# Sheet1.net
KiCad netlist of a schematic drawn in Altium Designer
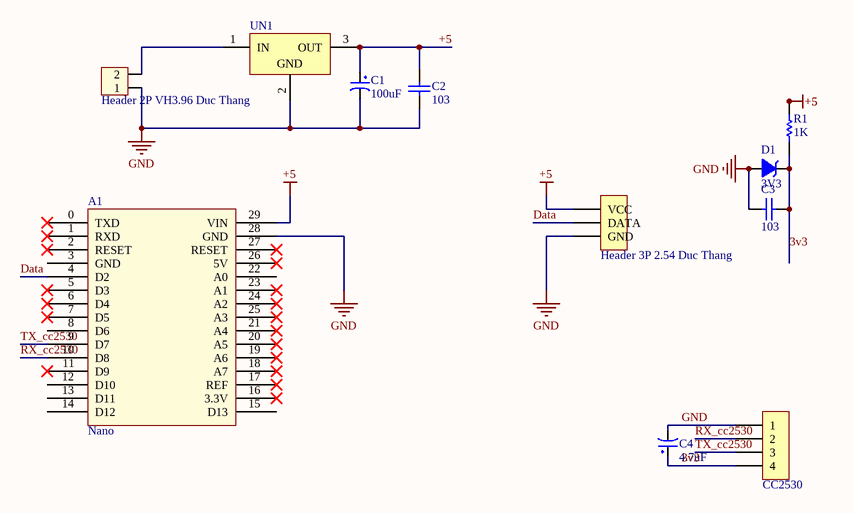
[diagram p0: Sheet1.SchDoc]

(export (version "E")
  (design (tool "Eeschema 10.0.6"))
  (components
    (comp (ref "A1")
      (value "Nano")
      (footprint "Arduino nano")
      (libsource (lib "Altium_Lib_by_KhueNguyenCreator") (part "Arduino Nano"))
    )
    (comp (ref "C1")
      (value "100uF")
      (footprint "tu hoa 5mm")
      (description "Cắm")
      (libsource (lib "Altium_Lib_by_KhueNguyenCreator") (part "Tu Hoa 100uF 16V 5x7"))
    )
    (comp (ref "C2")
      (value "103")
      (footprint "tu gom")
      (description "Cắm")
      (libsource (lib "Altium_Lib_by_KhueNguyenCreator") (part "Tu gom 103 50V"))
    )
    (comp (ref "C3")
      (value "103")
      (footprint "tu gom")
      (description "Cắm")
      (libsource (lib "Altium_Lib_by_KhueNguyenCreator") (part "Tu gom 103 50V"))
    )
    (comp (ref "C4")
      (value "4.7uF")
      (footprint "tu hoa 8mm")
      (description "Cắm")
      (libsource (lib "Altium_Lib_by_KhueNguyenCreator") (part "Tu Hoa 4.7uF 400V 8x12"))
    )
    (comp (ref "D1")
      (value "3V3")
      (footprint "DZ2A")
      (description "Diode Zenner")
      (libsource (lib "My library altium") (part "DZ"))
    )
    (comp (ref "H1")
      (value "Header 2P VH3.96 Duc Thang")
      (footprint "VH3.96M-2")
      (description "Cắm")
      (libsource (lib "Altium_Lib_by_KhueNguyenCreator") (part "Header 2P VH3.96 Duc Thang"))
    )
    (comp (ref "H2")
      (value "Header 3P 2.54 Duc Thang")
      (footprint "XH2.54M-3")
      (description "Cắm")
      (libsource (lib "Altium_Lib_by_KhueNguyenCreator") (part "Header 3P 2.54 Duc Thang"))
    )
    (comp (ref "H3")
      (value "CC2530")
      (footprint "XH2.54M-4")
      (description "Cắm")
      (libsource (lib "Altium_Lib_by_KhueNguyenCreator") (part "Header 4P 2.54 Duc Thang"))
    )
    (comp (ref "R1")
      (value "1K")
      (footprint "R1/4W")
      (description "Resistor")
      (fields
        (field (name "MANUFACTURER") "Generic Components")
        (field (name "Comment") "Res1")
        (field (name "PUBLISHER") "Altium Hobart Technology Centre")
      )
      (libsource (lib "syhaunguyen") (part "Res1_4"))
    )
    (comp (ref "UN1")
      (value "L78M05CP")
      (footprint "QTO-220H2")
      (description "Positive Voltage Regulator")
      (fields (field (name "PUBLISHER") "Altium Limited"))
      (libsource (lib "My library altium") (part "L78M05CP"))
    )
  )
  (nets
    (net (code "1") (name "+5") (class "Default")
      (node (ref "A1") (pin "29") (pinfunction "VIN_29") (pintype "passive"))
      (node (ref "C1") (pin "1") (pinfunction "1_1") (pintype "passive"))
      (node (ref "C2") (pin "1") (pinfunction "1_1") (pintype "passive"))
      (node (ref "H2") (pin "1") (pinfunction "VCC_1") (pintype "passive"))
      (node (ref "R1") (pin "2") (pinfunction "2_2") (pintype "passive"))
      (node (ref "UN1") (pin "3") (pinfunction "OUT_3") (pintype "power_in"))
    )
    (net (code "2") (name "/3v3") (class "Default")
      (node (ref "C3") (pin "1") (pinfunction "1_1") (pintype "passive"))
      (node (ref "C4") (pin "1") (pinfunction "1_1") (pintype "passive"))
      (node (ref "D1") (pin "2") (pinfunction "K_2") (pintype "passive"))
      (node (ref "H3") (pin "4") (pinfunction "4_4") (pintype "passive"))
      (node (ref "R1") (pin "1") (pinfunction "1_1") (pintype "passive"))
    )
    (net (code "3") (name "/Data") (class "Default")
      (node (ref "A1") (pin "4") (pinfunction "D2_4") (pintype "passive"))
      (node (ref "H2") (pin "2") (pinfunction "DATA_2") (pintype "passive"))
    )
    (net (code "4") (name "/RX_cc2530") (class "Default")
      (node (ref "A1") (pin "10") (pinfunction "D8_10") (pintype "passive"))
      (node (ref "H3") (pin "2") (pinfunction "2_2") (pintype "passive"))
    )
    (net (code "5") (name "/TX_cc2530") (class "Default")
      (node (ref "A1") (pin "9") (pinfunction "D7_9") (pintype "passive"))
      (node (ref "H3") (pin "3") (pinfunction "3_3") (pintype "passive"))
    )
    (net (code "6") (name "GND") (class "Default")
      (node (ref "A1") (pin "28") (pinfunction "GND_28") (pintype "passive"))
      (node (ref "C1") (pin "2") (pinfunction "2_2") (pintype "passive"))
      (node (ref "C2") (pin "2") (pinfunction "2_2") (pintype "passive"))
      (node (ref "C3") (pin "2") (pinfunction "2_2") (pintype "passive"))
      (node (ref "C4") (pin "2") (pinfunction "2_2") (pintype "passive"))
      (node (ref "D1") (pin "1") (pinfunction "A_1") (pintype "passive"))
      (node (ref "H1") (pin "1") (pinfunction "1_1") (pintype "passive"))
      (node (ref "H2") (pin "3") (pinfunction "GND_3") (pintype "passive"))
      (node (ref "H3") (pin "1") (pinfunction "1_1") (pintype "passive"))
      (node (ref "UN1") (pin "2") (pinfunction "GND_2") (pintype "power_in"))
    )
    (net (code "7") (name "Net-(UN1-IN)") (class "Default")
      (node (ref "H1") (pin "2") (pinfunction "2_2") (pintype "passive"))
      (node (ref "UN1") (pin "1") (pinfunction "IN_1") (pintype "power_in"))
    )
    (net (code "8") (name "unconnected-(A1-3.3V-Pad16)") (class "Default")
      (node (ref "A1") (pin "16") (pinfunction "3.3V_16") (pintype "passive+no_connect"))
    )
    (net (code "9") (name "unconnected-(A1-5V-Pad26)") (class "Default")
      (node (ref "A1") (pin "26") (pinfunction "5V_26") (pintype "passive+no_connect"))
    )
    (net (code "10") (name "unconnected-(A1-A0-Pad22)") (class "Default")
      (node (ref "A1") (pin "22") (pinfunction "A0_22") (pintype "passive"))
    )
    (net (code "11") (name "unconnected-(A1-A1-Pad23)") (class "Default")
      (node (ref "A1") (pin "23") (pinfunction "A1_23") (pintype "passive+no_connect"))
    )
    (net (code "12") (name "unconnected-(A1-A2-Pad24)") (class "Default")
      (node (ref "A1") (pin "24") (pinfunction "A2_24") (pintype "passive+no_connect"))
    )
    (net (code "13") (name "unconnected-(A1-A3-Pad25)") (class "Default")
      (node (ref "A1") (pin "25") (pinfunction "A3_25") (pintype "passive+no_connect"))
    )
    (net (code "14") (name "unconnected-(A1-A4-Pad21)") (class "Default")
      (node (ref "A1") (pin "21") (pinfunction "A4_21") (pintype "passive+no_connect"))
    )
    (net (code "15") (name "unconnected-(A1-A5-Pad20)") (class "Default")
      (node (ref "A1") (pin "20") (pinfunction "A5_20") (pintype "passive+no_connect"))
    )
    (net (code "16") (name "unconnected-(A1-A6-Pad19)") (class "Default")
      (node (ref "A1") (pin "19") (pinfunction "A6_19") (pintype "passive+no_connect"))
    )
    (net (code "17") (name "unconnected-(A1-A7-Pad18)") (class "Default")
      (node (ref "A1") (pin "18") (pinfunction "A7_18") (pintype "passive+no_connect"))
    )
    (net (code "18") (name "unconnected-(A1-D3-Pad5)") (class "Default")
      (node (ref "A1") (pin "5") (pinfunction "D3_5") (pintype "passive+no_connect"))
    )
    (net (code "19") (name "unconnected-(A1-D4-Pad6)") (class "Default")
      (node (ref "A1") (pin "6") (pinfunction "D4_6") (pintype "passive+no_connect"))
    )
    (net (code "20") (name "unconnected-(A1-D5-Pad7)") (class "Default")
      (node (ref "A1") (pin "7") (pinfunction "D5_7") (pintype "passive+no_connect"))
    )
    (net (code "21") (name "unconnected-(A1-D6-Pad8)") (class "Default")
      (node (ref "A1") (pin "8") (pinfunction "D6_8") (pintype "passive"))
    )
    (net (code "22") (name "unconnected-(A1-D9-Pad11)") (class "Default")
      (node (ref "A1") (pin "11") (pinfunction "D9_11") (pintype "passive+no_connect"))
    )
    (net (code "23") (name "unconnected-(A1-D10-Pad12)") (class "Default")
      (node (ref "A1") (pin "12") (pinfunction "D10_12") (pintype "passive"))
    )
    (net (code "24") (name "unconnected-(A1-D11-Pad13)") (class "Default")
      (node (ref "A1") (pin "13") (pinfunction "D11_13") (pintype "passive"))
    )
    (net (code "25") (name "unconnected-(A1-D12-Pad14)") (class "Default")
      (node (ref "A1") (pin "14") (pinfunction "D12_14") (pintype "passive"))
    )
    (net (code "26") (name "unconnected-(A1-D13-Pad15)") (class "Default")
      (node (ref "A1") (pin "15") (pinfunction "D13_15") (pintype "passive"))
    )
    (net (code "27") (name "unconnected-(A1-GND-Pad3)") (class "Default")
      (node (ref "A1") (pin "3") (pinfunction "GND_3") (pintype "passive"))
    )
    (net (code "28") (name "unconnected-(A1-REF-Pad17)") (class "Default")
      (node (ref "A1") (pin "17") (pinfunction "REF_17") (pintype "passive+no_connect"))
    )
    (net (code "29") (name "unconnected-(A1-RESET-Pad2)") (class "Default")
      (node (ref "A1") (pin "2") (pinfunction "RESET_2") (pintype "passive+no_connect"))
    )
    (net (code "30") (name "unconnected-(A1-RESET-Pad27)") (class "Default")
      (node (ref "A1") (pin "27") (pinfunction "RESET_27") (pintype "passive+no_connect"))
    )
    (net (code "31") (name "unconnected-(A1-RXD-Pad1)") (class "Default")
      (node (ref "A1") (pin "1") (pinfunction "RXD_1") (pintype "passive+no_connect"))
    )
    (net (code "32") (name "unconnected-(A1-TXD-Pad0)") (class "Default")
      (node (ref "A1") (pin "0") (pinfunction "TXD_0") (pintype "passive+no_connect"))
    )
  )
)
